# compare5_1.net
KiCad netlist of a schematic drawn in EAGLE
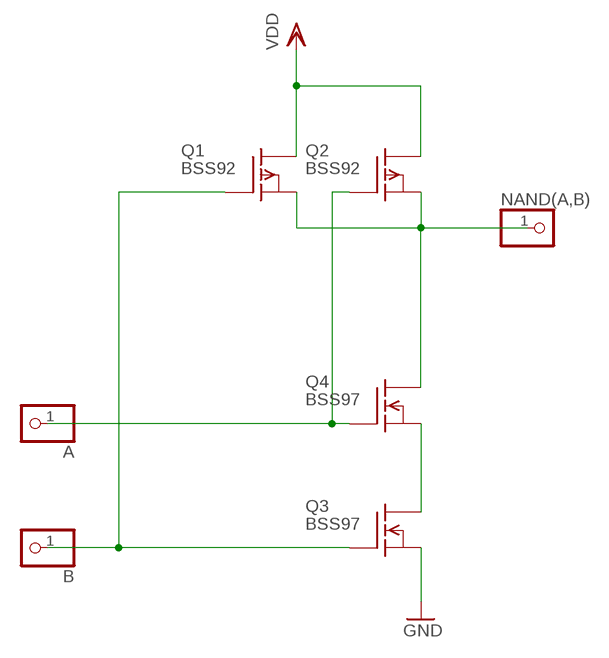
[diagram p0: schematic, sheet 1]

(export (version "E")
  (design (tool "Eeschema 10.0.6"))
  (components
    (comp (ref "A")
      (value "PINHD-1X1")
      (footprint "eagle-import:1X01")
      (libsource (lib "eagle-import") (part "PINHD-1X1"))
    )
    (comp (ref "B")
      (value "PINHD-1X1")
      (footprint "eagle-import:1X01")
      (libsource (lib "eagle-import") (part "PINHD-1X1"))
    )
    (comp (ref "NAND(A,B)")
      (value "PINHD-1X1")
      (footprint "eagle-import:1X01")
      (libsource (lib "eagle-import") (part "PINHD-1X1"))
    )
    (comp (ref "Q1")
      (value "BSS92")
      (footprint "eagle-import:TO92")
      (libsource (lib "eagle-import") (part "BSS92"))
    )
    (comp (ref "Q2")
      (value "BSS92")
      (footprint "eagle-import:TO92")
      (libsource (lib "eagle-import") (part "BSS92"))
    )
    (comp (ref "Q3")
      (value "BSS97")
      (footprint "eagle-import:TO202")
      (libsource (lib "eagle-import") (part "BSS97"))
    )
    (comp (ref "Q4")
      (value "BSS97")
      (footprint "eagle-import:TO202")
      (libsource (lib "eagle-import") (part "BSS97"))
    )
  )
  (nets
    (net (code "1") (name "GND") (class "Default")
      (node (ref "Q3") (pin "1") (pinfunction "S_1") (pintype "passive"))
    )
    (net (code "2") (name "Net-(Q1-G)") (class "Default")
      (node (ref "B") (pin "1") (pinfunction "1_1") (pintype "passive"))
      (node (ref "Q1") (pin "1") (pinfunction "G_1") (pintype "passive"))
      (node (ref "Q3") (pin "3") (pinfunction "G_3") (pintype "passive"))
    )
    (net (code "3") (name "Net-(Q1-S)") (class "Default")
      (node (ref "NAND(A,B)") (pin "1") (pinfunction "1_1") (pintype "passive"))
      (node (ref "Q1") (pin "3") (pinfunction "S_3") (pintype "passive"))
      (node (ref "Q2") (pin "3") (pinfunction "S_3") (pintype "passive"))
      (node (ref "Q4") (pin "2") (pinfunction "D_2") (pintype "passive"))
    )
    (net (code "4") (name "Net-(Q2-G)") (class "Default")
      (node (ref "A") (pin "1") (pinfunction "1_1") (pintype "passive"))
      (node (ref "Q2") (pin "1") (pinfunction "G_1") (pintype "passive"))
      (node (ref "Q4") (pin "3") (pinfunction "G_3") (pintype "passive"))
    )
    (net (code "5") (name "Net-(Q3-D)") (class "Default")
      (node (ref "Q3") (pin "2") (pinfunction "D_2") (pintype "passive"))
      (node (ref "Q4") (pin "1") (pinfunction "S_1") (pintype "passive"))
    )
    (net (code "6") (name "VDD") (class "Default")
      (node (ref "Q1") (pin "2") (pinfunction "D_2") (pintype "passive"))
      (node (ref "Q2") (pin "2") (pinfunction "D_2") (pintype "passive"))
    )
  )
)
